# MS5607_Breakout.net
KiCad netlist of a schematic drawn in EAGLE
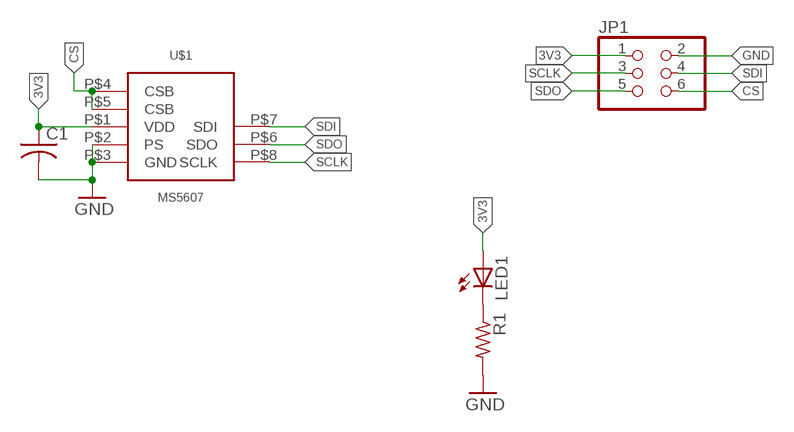
[diagram p0: schematic, sheet 1]

(export (version "E")
  (design (tool "Eeschema 10.0.6"))
  (components
    (comp (ref "C1")
      (value "C-USC0805")
      (footprint "eagle-import:C0805")
      (libsource (lib "eagle-import") (part "C-USC0805"))
    )
    (comp (ref "JP1")
      (value "PINHD-2X3")
      (footprint "eagle-import:2X03")
      (libsource (lib "eagle-import") (part "PINHD-2X3"))
    )
    (comp (ref "LED1")
      (value "LEDCHIPLED_0805")
      (footprint "eagle-import:CHIPLED_0805")
      (libsource (lib "eagle-import") (part "LEDCHIPLED_0805"))
    )
    (comp (ref "R1")
      (value "R-US_R0805")
      (footprint "eagle-import:R0805")
      (libsource (lib "eagle-import") (part "R-US_R0805"))
    )
    (comp (ref "U$1")
      (value "MS5607")
      (footprint "eagle-import:MS5607")
      (libsource (lib "eagle-import") (part "MS5607"))
    )
  )
  (nets
    (net (code "1") (name "3V3") (class "Default")
      (node (ref "C1") (pin "1") (pinfunction "1_1") (pintype "passive"))
      (node (ref "JP1") (pin "1") (pinfunction "1_1") (pintype "passive"))
      (node (ref "LED1") (pin "A") (pinfunction "A_A") (pintype "passive"))
      (node (ref "U$1") (pin "P$1") (pinfunction "VDD_P$1") (pintype "bidirectional"))
    )
    (net (code "2") (name "CS") (class "Default")
      (node (ref "JP1") (pin "6") (pinfunction "6_6") (pintype "passive"))
      (node (ref "U$1") (pin "P$4") (pinfunction "CSB_P$4") (pintype "bidirectional"))
      (node (ref "U$1") (pin "P$5") (pinfunction "CSB_P$5") (pintype "bidirectional"))
    )
    (net (code "3") (name "GND") (class "Default")
      (node (ref "C1") (pin "2") (pinfunction "2_2") (pintype "passive"))
      (node (ref "JP1") (pin "2") (pinfunction "2_2") (pintype "passive"))
      (node (ref "R1") (pin "2") (pinfunction "2_2") (pintype "passive"))
      (node (ref "U$1") (pin "P$2") (pinfunction "PS_P$2") (pintype "bidirectional"))
      (node (ref "U$1") (pin "P$3") (pinfunction "GND_P$3") (pintype "bidirectional"))
    )
    (net (code "4") (name "Net-(LED1-PadC)") (class "Default")
      (node (ref "LED1") (pin "C") (pinfunction "C_C") (pintype "passive"))
      (node (ref "R1") (pin "1") (pinfunction "1_1") (pintype "passive"))
    )
    (net (code "5") (name "SCLK") (class "Default")
      (node (ref "JP1") (pin "3") (pinfunction "3_3") (pintype "passive"))
      (node (ref "U$1") (pin "P$8") (pinfunction "SCLK_P$8") (pintype "bidirectional"))
    )
    (net (code "6") (name "SDI") (class "Default")
      (node (ref "JP1") (pin "4") (pinfunction "4_4") (pintype "passive"))
      (node (ref "U$1") (pin "P$7") (pinfunction "SDI_P$7") (pintype "bidirectional"))
    )
    (net (code "7") (name "SDO") (class "Default")
      (node (ref "JP1") (pin "5") (pinfunction "5_5") (pintype "passive"))
      (node (ref "U$1") (pin "P$6") (pinfunction "SDO_P$6") (pintype "bidirectional"))
    )
  )
)
